# 31.net
KiCad netlist of a schematic drawn in Altium Designer
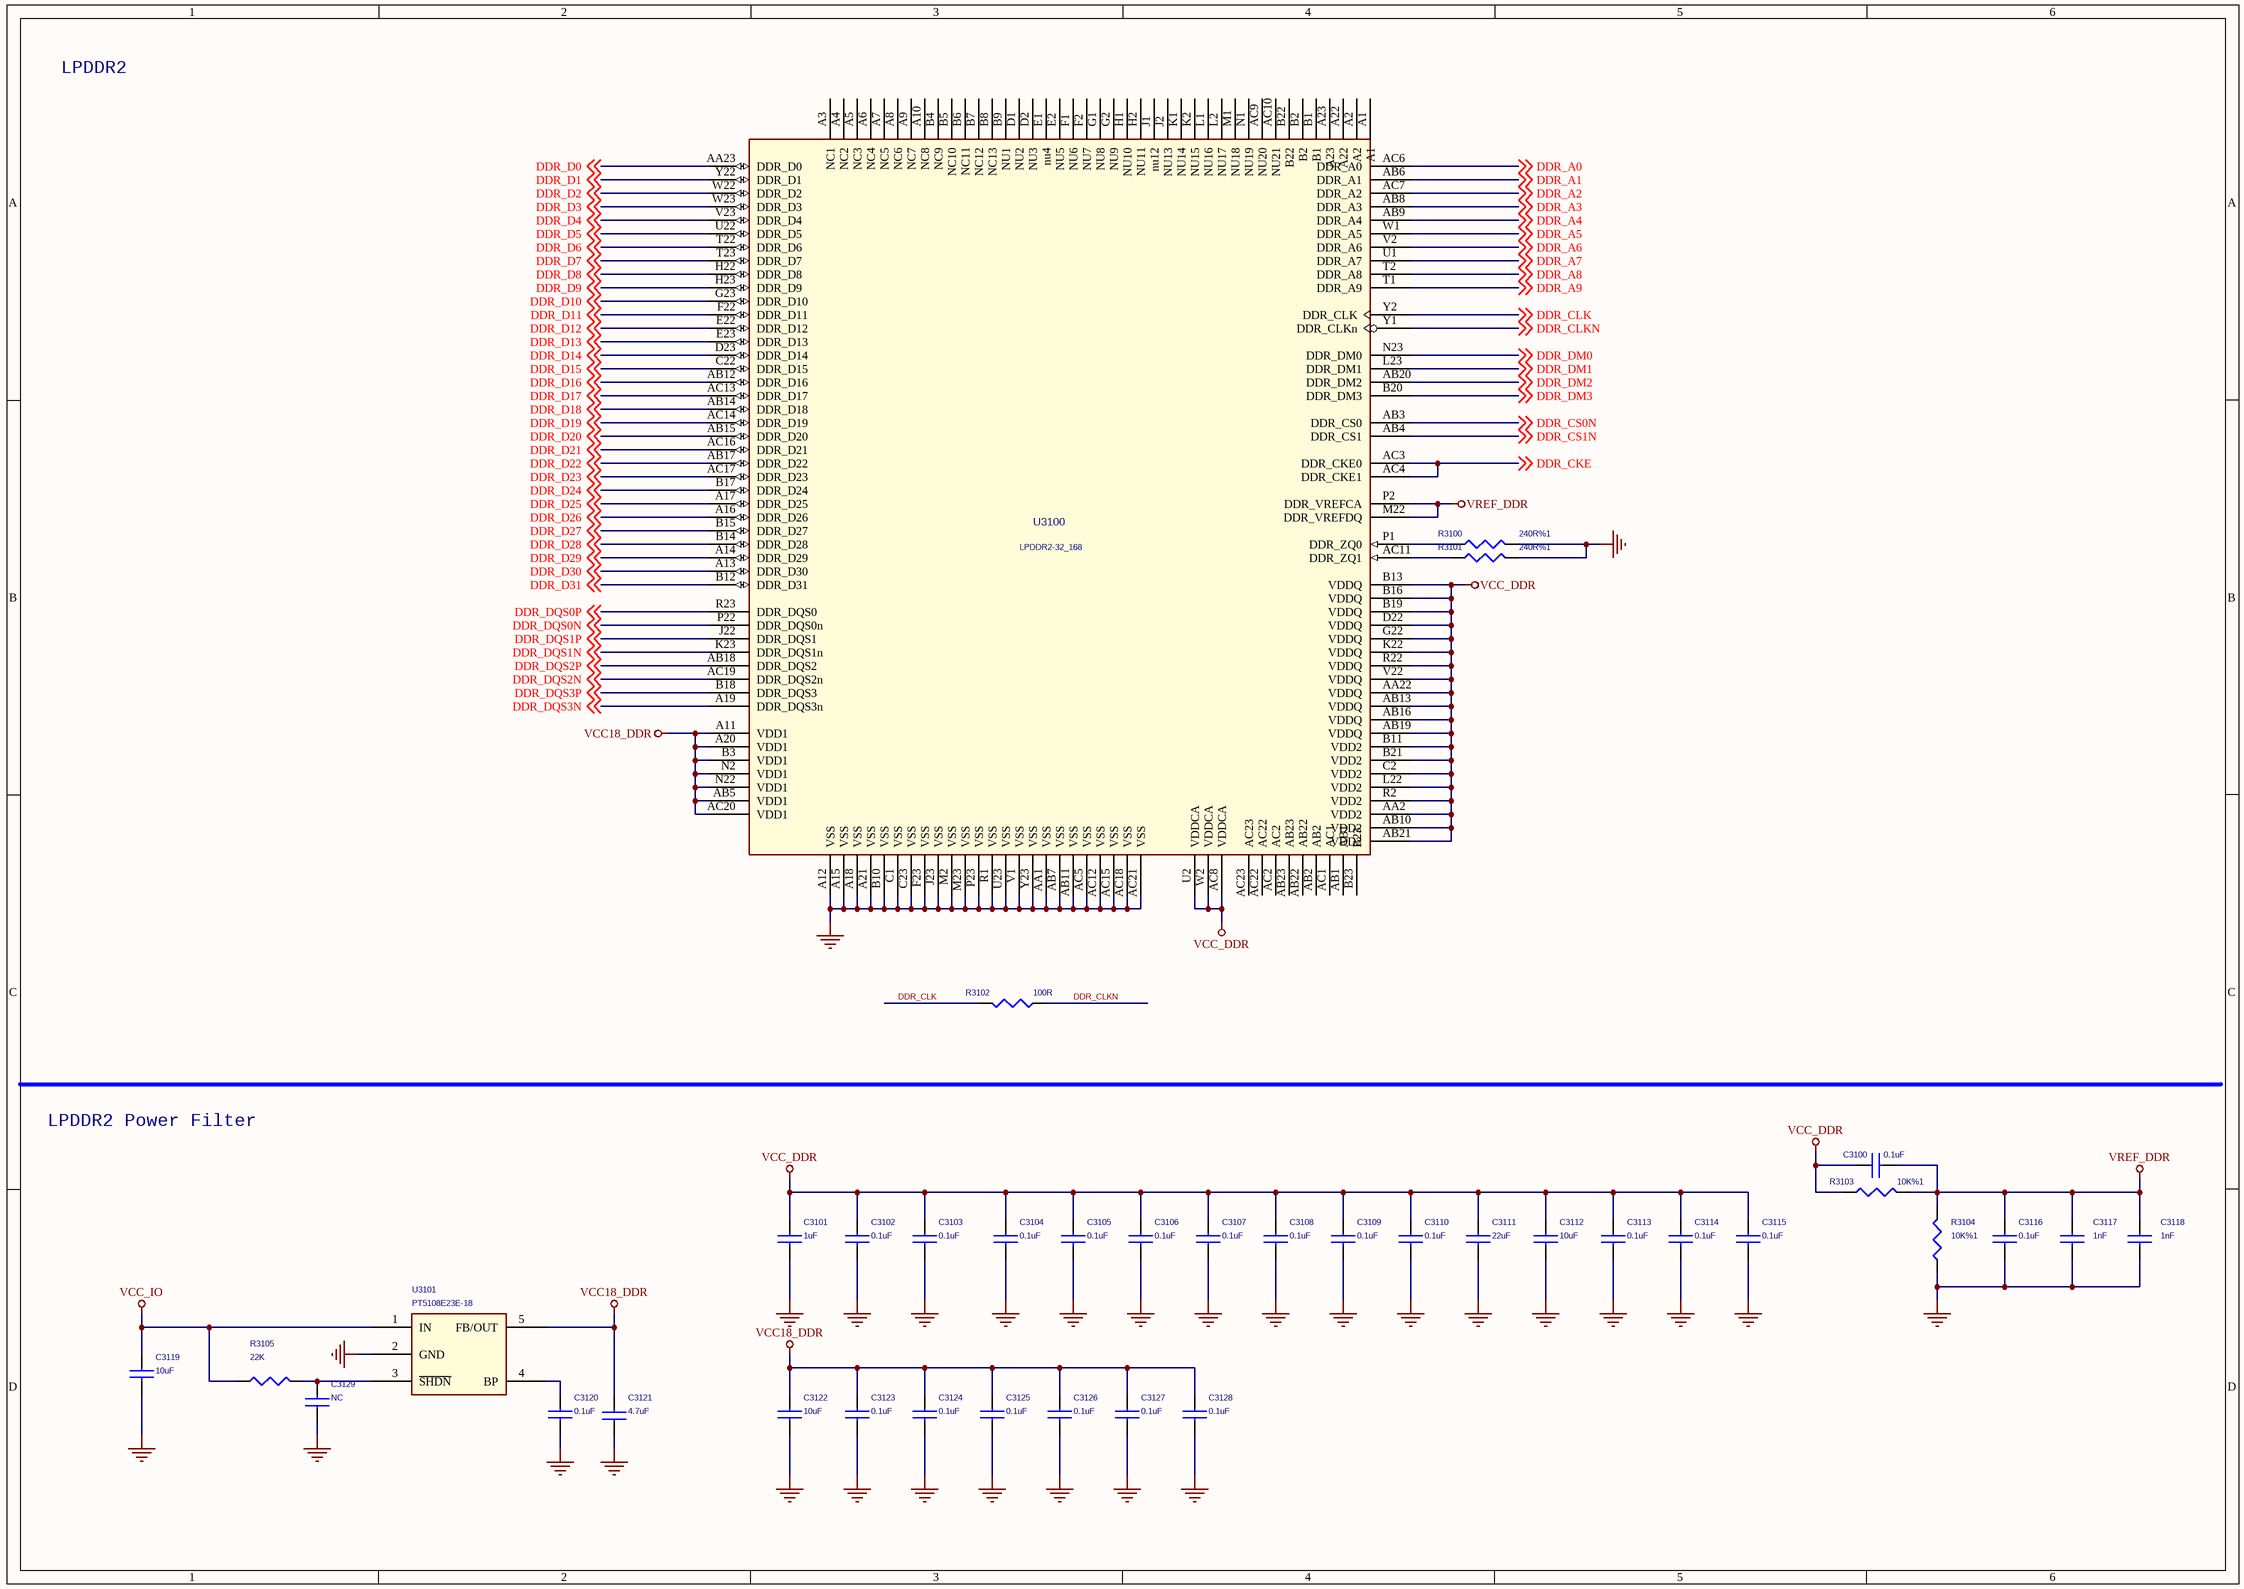
[diagram p0: 31.SchDoc]

(export (version "E")
  (design (tool "Eeschema 10.0.6"))
  (components
    (comp (ref "C3100") (value "0.1uF") (footprint "C0402") (libsource (lib "*") (part "CAP NP_0")))
    (comp (ref "C3101")
      (value "1uF")
      (footprint "C0402")
      (description "RoHS CHIP CAP 1uF +10/-10% X5R")
      (libsource (lib "*") (part "CAP NP"))
    )
    (comp (ref "C3102")
      (value "0.1uF")
      (footprint "C0402")
      (description "RoHS CHIP CAP 1uF +10/-10% X5R")
      (libsource (lib "*") (part "CAP NP"))
    )
    (comp (ref "C3103")
      (value "0.1uF")
      (footprint "C0402")
      (description "RoHS CHIP CAP 0.1uF +10/-10% X7R")
      (libsource (lib "*") (part "CAP NP"))
    )
    (comp (ref "C3104")
      (value "0.1uF")
      (footprint "C0402")
      (description "RoHS CHIP CAP 0.1uF +10/-10% X7R")
      (libsource (lib "*") (part "CAP NP"))
    )
    (comp (ref "C3105")
      (value "0.1uF")
      (footprint "C0402")
      (description "RoHS CHIP CAP 0.1uF +10/-10% X7R")
      (libsource (lib "*") (part "CAP NP"))
    )
    (comp (ref "C3106")
      (value "0.1uF")
      (footprint "C0402")
      (description "RoHS CHIP CAP 0.1uF +10/-10% X7R")
      (libsource (lib "*") (part "CAP NP"))
    )
    (comp (ref "C3107")
      (value "0.1uF")
      (footprint "C0402")
      (description "RoHS CHIP CAP 0.1uF +10/-10% X7R")
      (libsource (lib "*") (part "CAP NP"))
    )
    (comp (ref "C3108")
      (value "0.1uF")
      (footprint "C0402")
      (description "RoHS CHIP CAP 0.1uF +10/-10% X7R")
      (libsource (lib "*") (part "CAP NP"))
    )
    (comp (ref "C3109")
      (value "0.1uF")
      (footprint "C0402")
      (description "RoHS CHIP CAP 0.1uF +10/-10% X7R")
      (libsource (lib "*") (part "CAP NP"))
    )
    (comp (ref "C3110")
      (value "0.1uF")
      (footprint "C0402")
      (description "RoHS CHIP CAP 0.1uF +10/-10% X7R")
      (libsource (lib "*") (part "CAP NP"))
    )
    (comp (ref "C3111")
      (value "22uF")
      (footprint "C0402")
      (description "RoHS CHIP CAP 0.1uF +10/-10% X7R")
      (libsource (lib "*") (part "CAP NP"))
    )
    (comp (ref "C3112")
      (value "10uF")
      (footprint "C0402")
      (description "RoHS CHIP CAP 0.1uF +10/-10% X7R")
      (libsource (lib "*") (part "CAP NP"))
    )
    (comp (ref "C3113")
      (value "0.1uF")
      (footprint "C0402")
      (description "RoHS CHIP CAP 0.1uF +10/-10% X7R")
      (libsource (lib "*") (part "CAP NP"))
    )
    (comp (ref "C3114")
      (value "0.1uF")
      (footprint "C0402")
      (description "RoHS CHIP CAP 0.1uF +10/-10% X7R")
      (libsource (lib "*") (part "CAP NP"))
    )
    (comp (ref "C3115")
      (value "0.1uF")
      (footprint "C0402")
      (description "RoHS CHIP CAP 0.1uF +10/-10% X7R")
      (libsource (lib "*") (part "CAP NP"))
    )
    (comp (ref "C3116") (value "0.1uF") (footprint "C0402") (libsource (lib "*") (part "CAP NP_0")))
    (comp (ref "C3117") (value "1nF") (footprint "C0402") (libsource (lib "*") (part "CAP NP_0")))
    (comp (ref "C3118") (value "1nF") (footprint "C0402") (libsource (lib "*") (part "CAP NP_0")))
    (comp (ref "C3119")
      (value "10uF")
      (footprint "C0402")
      (description "CAP,MLCC,22uF,+/-10%,X5R,6.3V,SMD1206")
      (libsource (lib "*") (part "CAP NP"))
    )
    (comp (ref "C3120")
      (value "0.1uF")
      (footprint "C0402")
      (description "CAP,MLCC,100nF,+/-10%,X7R,6.3V,SMD0402")
      (libsource (lib "*") (part "CAP NP"))
    )
    (comp (ref "C3121")
      (value "4.7uF")
      (footprint "C0402")
      (description "CAP,MLCC,10uF,+/-10%,X5R,6.3V,SMD0805")
      (libsource (lib "*") (part "CAP NP"))
    )
    (comp (ref "C3122")
      (value "10uF")
      (footprint "C0402")
      (description "RoHS CHIP CAP 1uF +10/-10% X5R")
      (libsource (lib "*") (part "CAP NP"))
    )
    (comp (ref "C3123")
      (value "0.1uF")
      (footprint "C0402")
      (description "RoHS CHIP CAP 0.1uF +10/-10% X7R")
      (libsource (lib "*") (part "CAP NP"))
    )
    (comp (ref "C3124")
      (value "0.1uF")
      (footprint "C0402")
      (description "RoHS CHIP CAP 0.1uF +10/-10% X7R")
      (libsource (lib "*") (part "CAP NP"))
    )
    (comp (ref "C3125")
      (value "0.1uF")
      (footprint "C0402")
      (description "RoHS CHIP CAP 0.1uF +10/-10% X7R")
      (libsource (lib "*") (part "CAP NP"))
    )
    (comp (ref "C3126")
      (value "0.1uF")
      (footprint "C0402")
      (description "RoHS CHIP CAP 0.1uF +10/-10% X7R")
      (libsource (lib "*") (part "CAP NP"))
    )
    (comp (ref "C3127")
      (value "0.1uF")
      (footprint "C0402")
      (description "RoHS CHIP CAP 0.1uF +10/-10% X7R")
      (libsource (lib "*") (part "CAP NP"))
    )
    (comp (ref "C3128")
      (value "0.1uF")
      (footprint "C0402")
      (description "RoHS CHIP CAP 0.1uF +10/-10% X7R")
      (libsource (lib "*") (part "CAP NP"))
    )
    (comp (ref "C3129") (value "NC") (footprint "C0402") (libsource (lib "*") (part "CAP NP")))
    (comp (ref "R3100")
      (value "240R%1")
      (footprint "R0402")
      (description "贴片电阻")
      (libsource (lib "*") (part "RESISTOR_0"))
    )
    (comp (ref "R3101")
      (value "240R%1")
      (footprint "R0402")
      (description "贴片电阻")
      (libsource (lib "*") (part "RESISTOR_0"))
    )
    (comp (ref "R3102")
      (value "100R")
      (footprint "R0402")
      (description "NC/ROHS CHIP RES 100R 1/16W 5%")
      (libsource (lib "*") (part "RESISTOR"))
    )
    (comp (ref "R3103")
      (value "10K%1")
      (footprint "R0402")
      (description "贴片电阻")
      (libsource (lib "*") (part "RESISTOR_0"))
    )
    (comp (ref "R3104")
      (value "10K%1")
      (footprint "R0402")
      (description "贴片电阻")
      (libsource (lib "*") (part "RESISTOR_0"))
    )
    (comp (ref "R3105") (value "22K") (footprint "R0402") (libsource (lib "*") (part "RES 1B")))
    (comp (ref "U3100")
      (value "LPDDR2-32_168")
      (footprint "BGA134")
      (libsource (lib "*") (part "LPDDR2-32_2"))
    )
    (comp (ref "U3101")
      (value "PT5108E23E-18")
      (footprint "SOT25")
      (description "LDO,PT5108E23E-18,VINmax=5.5V,Vout=1.8V,+/-2%,500mA,SOT-23-5")
      (libsource (lib "*") (part "DS8008_4"))
    )
  )
  (nets
    (net (code "1") (name "DDR_A0") (class "Default")
      (node (ref "U3100") (pin "AC6") (pinfunction "DDR_A0_AC6") (pintype "passive"))
    )
    (net (code "2") (name "DDR_A1") (class "Default")
      (node (ref "U3100") (pin "AB6") (pinfunction "DDR_A1_AB6") (pintype "passive"))
    )
    (net (code "3") (name "DDR_A2") (class "Default")
      (node (ref "U3100") (pin "AC7") (pinfunction "DDR_A2_AC7") (pintype "passive"))
    )
    (net (code "4") (name "DDR_A3") (class "Default")
      (node (ref "U3100") (pin "AB8") (pinfunction "DDR_A3_AB8") (pintype "passive"))
    )
    (net (code "5") (name "DDR_A4") (class "Default")
      (node (ref "U3100") (pin "AB9") (pinfunction "DDR_A4_AB9") (pintype "passive"))
    )
    (net (code "6") (name "DDR_A5") (class "Default")
      (node (ref "U3100") (pin "W1") (pinfunction "DDR_A5_W1") (pintype "passive"))
    )
    (net (code "7") (name "DDR_A6") (class "Default")
      (node (ref "U3100") (pin "V2") (pinfunction "DDR_A6_V2") (pintype "passive"))
    )
    (net (code "8") (name "DDR_A7") (class "Default")
      (node (ref "U3100") (pin "U1") (pinfunction "DDR_A7_U1") (pintype "passive"))
    )
    (net (code "9") (name "DDR_A8") (class "Default")
      (node (ref "U3100") (pin "T2") (pinfunction "DDR_A8_T2") (pintype "passive"))
    )
    (net (code "10") (name "DDR_A9") (class "Default")
      (node (ref "U3100") (pin "T1") (pinfunction "DDR_A9_T1") (pintype "passive"))
    )
    (net (code "11") (name "DDR_CKE") (class "Default")
      (node (ref "U3100") (pin "AC3") (pinfunction "DDR_CKE0_AC3") (pintype "passive"))
      (node (ref "U3100") (pin "AC4") (pinfunction "DDR_CKE1_AC4") (pintype "passive"))
    )
    (net (code "12") (name "DDR_CLK") (class "Default")
      (node (ref "R3102") (pin "2") (pinfunction "2_2") (pintype "passive"))
      (node (ref "U3100") (pin "Y2") (pinfunction "DDR_CLK_Y2") (pintype "passive"))
    )
    (net (code "13") (name "DDR_CLKN") (class "Default")
      (node (ref "R3102") (pin "1") (pinfunction "1_1") (pintype "passive"))
      (node (ref "U3100") (pin "Y1") (pinfunction "DDR_CLKn_Y1") (pintype "passive"))
    )
    (net (code "14") (name "DDR_CS0N") (class "Default")
      (node (ref "U3100") (pin "AB3") (pinfunction "DDR_CS0_AB3") (pintype "passive"))
    )
    (net (code "15") (name "DDR_CS1N") (class "Default")
      (node (ref "U3100") (pin "AB4") (pinfunction "DDR_CS1_AB4") (pintype "passive"))
    )
    (net (code "16") (name "DDR_D0") (class "Default")
      (node (ref "U3100") (pin "AA23") (pinfunction "DDR_D0_AA23") (pintype "bidirectional"))
    )
    (net (code "17") (name "DDR_D1") (class "Default")
      (node (ref "U3100") (pin "Y22") (pinfunction "DDR_D1_Y22") (pintype "bidirectional"))
    )
    (net (code "18") (name "DDR_D2") (class "Default")
      (node (ref "U3100") (pin "W22") (pinfunction "DDR_D2_W22") (pintype "bidirectional"))
    )
    (net (code "19") (name "DDR_D3") (class "Default")
      (node (ref "U3100") (pin "W23") (pinfunction "DDR_D3_W23") (pintype "bidirectional"))
    )
    (net (code "20") (name "DDR_D4") (class "Default")
      (node (ref "U3100") (pin "V23") (pinfunction "DDR_D4_V23") (pintype "bidirectional"))
    )
    (net (code "21") (name "DDR_D5") (class "Default")
      (node (ref "U3100") (pin "U22") (pinfunction "DDR_D5_U22") (pintype "bidirectional"))
    )
    (net (code "22") (name "DDR_D6") (class "Default")
      (node (ref "U3100") (pin "T22") (pinfunction "DDR_D6_T22") (pintype "bidirectional"))
    )
    (net (code "23") (name "DDR_D7") (class "Default")
      (node (ref "U3100") (pin "T23") (pinfunction "DDR_D7_T23") (pintype "bidirectional"))
    )
    (net (code "24") (name "DDR_D8") (class "Default")
      (node (ref "U3100") (pin "H22") (pinfunction "DDR_D8_H22") (pintype "bidirectional"))
    )
    (net (code "25") (name "DDR_D9") (class "Default")
      (node (ref "U3100") (pin "H23") (pinfunction "DDR_D9_H23") (pintype "bidirectional"))
    )
    (net (code "26") (name "DDR_D10") (class "Default")
      (node (ref "U3100") (pin "G23") (pinfunction "DDR_D10_G23") (pintype "bidirectional"))
    )
    (net (code "27") (name "DDR_D11") (class "Default")
      (node (ref "U3100") (pin "F22") (pinfunction "DDR_D11_F22") (pintype "bidirectional"))
    )
    (net (code "28") (name "DDR_D12") (class "Default")
      (node (ref "U3100") (pin "E22") (pinfunction "DDR_D12_E22") (pintype "bidirectional"))
    )
    (net (code "29") (name "DDR_D13") (class "Default")
      (node (ref "U3100") (pin "E23") (pinfunction "DDR_D13_E23") (pintype "bidirectional"))
    )
    (net (code "30") (name "DDR_D14") (class "Default")
      (node (ref "U3100") (pin "D23") (pinfunction "DDR_D14_D23") (pintype "bidirectional"))
    )
    (net (code "31") (name "DDR_D15") (class "Default")
      (node (ref "U3100") (pin "C22") (pinfunction "DDR_D15_C22") (pintype "bidirectional"))
    )
    (net (code "32") (name "DDR_D16") (class "Default")
      (node (ref "U3100") (pin "AB12") (pinfunction "DDR_D16_AB12") (pintype "bidirectional"))
    )
    (net (code "33") (name "DDR_D17") (class "Default")
      (node (ref "U3100") (pin "AC13") (pinfunction "DDR_D17_AC13") (pintype "bidirectional"))
    )
    (net (code "34") (name "DDR_D18") (class "Default")
      (node (ref "U3100") (pin "AB14") (pinfunction "DDR_D18_AB14") (pintype "bidirectional"))
    )
    (net (code "35") (name "DDR_D19") (class "Default")
      (node (ref "U3100") (pin "AC14") (pinfunction "DDR_D19_AC14") (pintype "bidirectional"))
    )
    (net (code "36") (name "DDR_D20") (class "Default")
      (node (ref "U3100") (pin "AB15") (pinfunction "DDR_D20_AB15") (pintype "bidirectional"))
    )
    (net (code "37") (name "DDR_D21") (class "Default")
      (node (ref "U3100") (pin "AC16") (pinfunction "DDR_D21_AC16") (pintype "bidirectional"))
    )
    (net (code "38") (name "DDR_D22") (class "Default")
      (node (ref "U3100") (pin "AB17") (pinfunction "DDR_D22_AB17") (pintype "bidirectional"))
    )
    (net (code "39") (name "DDR_D23") (class "Default")
      (node (ref "U3100") (pin "AC17") (pinfunction "DDR_D23_AC17") (pintype "bidirectional"))
    )
    (net (code "40") (name "DDR_D24") (class "Default")
      (node (ref "U3100") (pin "B17") (pinfunction "DDR_D24_B17") (pintype "bidirectional"))
    )
    (net (code "41") (name "DDR_D25") (class "Default")
      (node (ref "U3100") (pin "A17") (pinfunction "DDR_D25_A17") (pintype "bidirectional"))
    )
    (net (code "42") (name "DDR_D26") (class "Default")
      (node (ref "U3100") (pin "A16") (pinfunction "DDR_D26_A16") (pintype "bidirectional"))
    )
    (net (code "43") (name "DDR_D27") (class "Default")
      (node (ref "U3100") (pin "B15") (pinfunction "DDR_D27_B15") (pintype "bidirectional"))
    )
    (net (code "44") (name "DDR_D28") (class "Default")
      (node (ref "U3100") (pin "B14") (pinfunction "DDR_D28_B14") (pintype "bidirectional"))
    )
    (net (code "45") (name "DDR_D29") (class "Default")
      (node (ref "U3100") (pin "A14") (pinfunction "DDR_D29_A14") (pintype "bidirectional"))
    )
    (net (code "46") (name "DDR_D30") (class "Default")
      (node (ref "U3100") (pin "A13") (pinfunction "DDR_D30_A13") (pintype "bidirectional"))
    )
    (net (code "47") (name "DDR_D31") (class "Default")
      (node (ref "U3100") (pin "B12") (pinfunction "DDR_D31_B12") (pintype "bidirectional"))
    )
    (net (code "48") (name "DDR_DM0") (class "Default")
      (node (ref "U3100") (pin "N23") (pinfunction "DDR_DM0_N23") (pintype "passive"))
    )
    (net (code "49") (name "DDR_DM1") (class "Default")
      (node (ref "U3100") (pin "L23") (pinfunction "DDR_DM1_L23") (pintype "passive"))
    )
    (net (code "50") (name "DDR_DM2") (class "Default")
      (node (ref "U3100") (pin "AB20") (pinfunction "DDR_DM2_AB20") (pintype "passive"))
    )
    (net (code "51") (name "DDR_DM3") (class "Default")
      (node (ref "U3100") (pin "B20") (pinfunction "DDR_DM3_B20") (pintype "passive"))
    )
    (net (code "52") (name "DDR_DQS0N") (class "Default")
      (node (ref "U3100") (pin "P22") (pinfunction "DDR_DQS0n_P22") (pintype "passive"))
    )
    (net (code "53") (name "DDR_DQS0P") (class "Default")
      (node (ref "U3100") (pin "R23") (pinfunction "DDR_DQS0_R23") (pintype "passive"))
    )
    (net (code "54") (name "DDR_DQS1N") (class "Default")
      (node (ref "U3100") (pin "K23") (pinfunction "DDR_DQS1n_K23") (pintype "passive"))
    )
    (net (code "55") (name "DDR_DQS1P") (class "Default")
      (node (ref "U3100") (pin "J22") (pinfunction "DDR_DQS1_J22") (pintype "passive"))
    )
    (net (code "56") (name "DDR_DQS2N") (class "Default")
      (node (ref "U3100") (pin "AC19") (pinfunction "DDR_DQS2n_AC19") (pintype "passive"))
    )
    (net (code "57") (name "DDR_DQS2P") (class "Default")
      (node (ref "U3100") (pin "AB18") (pinfunction "DDR_DQS2_AB18") (pintype "passive"))
    )
    (net (code "58") (name "DDR_DQS3N") (class "Default")
      (node (ref "U3100") (pin "A19") (pinfunction "DDR_DQS3n_A19") (pintype "passive"))
    )
    (net (code "59") (name "DDR_DQS3P") (class "Default")
      (node (ref "U3100") (pin "B18") (pinfunction "DDR_DQS3_B18") (pintype "passive"))
    )
    (net (code "60") (name "GND") (class "Default")
      (node (ref "C3101") (pin "2") (pinfunction "2_2") (pintype "passive"))
      (node (ref "C3102") (pin "2") (pinfunction "2_2") (pintype "passive"))
      (node (ref "C3103") (pin "2") (pinfunction "2_2") (pintype "passive"))
      (node (ref "C3104") (pin "2") (pinfunction "2_2") (pintype "passive"))
      (node (ref "C3105") (pin "2") (pinfunction "2_2") (pintype "passive"))
      (node (ref "C3106") (pin "2") (pinfunction "2_2") (pintype "passive"))
      (node (ref "C3107") (pin "2") (pinfunction "2_2") (pintype "passive"))
      (node (ref "C3108") (pin "2") (pinfunction "2_2") (pintype "passive"))
      (node (ref "C3109") (pin "2") (pinfunction "2_2") (pintype "passive"))
      (node (ref "C3110") (pin "2") (pinfunction "2_2") (pintype "passive"))
      (node (ref "C3111") (pin "2") (pinfunction "2_2") (pintype "passive"))
      (node (ref "C3112") (pin "2") (pinfunction "2_2") (pintype "passive"))
      (node (ref "C3113") (pin "2") (pinfunction "2_2") (pintype "passive"))
      (node (ref "C3114") (pin "2") (pinfunction "2_2") (pintype "passive"))
      (node (ref "C3115") (pin "2") (pinfunction "2_2") (pintype "passive"))
      (node (ref "C3116") (pin "2") (pinfunction "2_2") (pintype "passive"))
      (node (ref "C3117") (pin "2") (pinfunction "2_2") (pintype "passive"))
      (node (ref "C3118") (pin "2") (pinfunction "2_2") (pintype "passive"))
      (node (ref "C3119") (pin "2") (pinfunction "2_2") (pintype "passive"))
      (node (ref "C3120") (pin "2") (pinfunction "2_2") (pintype "passive"))
      (node (ref "C3121") (pin "1") (pinfunction "1_1") (pintype "passive"))
      (node (ref "C3122") (pin "2") (pinfunction "2_2") (pintype "passive"))
      (node (ref "C3123") (pin "2") (pinfunction "2_2") (pintype "passive"))
      (node (ref "C3124") (pin "2") (pinfunction "2_2") (pintype "passive"))
      (node (ref "C3125") (pin "2") (pinfunction "2_2") (pintype "passive"))
      (node (ref "C3126") (pin "2") (pinfunction "2_2") (pintype "passive"))
      (node (ref "C3127") (pin "2") (pinfunction "2_2") (pintype "passive"))
      (node (ref "C3128") (pin "2") (pinfunction "2_2") (pintype "passive"))
      (node (ref "C3129") (pin "1") (pinfunction "1_1") (pintype "passive"))
      (node (ref "R3100") (pin "2") (pinfunction "2_2") (pintype "passive"))
      (node (ref "R3101") (pin "2") (pinfunction "2_2") (pintype "passive"))
      (node (ref "R3104") (pin "1") (pinfunction "1_1") (pintype "passive"))
      (node (ref "U3100") (pin "A12") (pinfunction "VSS_A12") (pintype "power_in"))
      (node (ref "U3100") (pin "A15") (pinfunction "VSS_A15") (pintype "power_in"))
      (node (ref "U3100") (pin "A18") (pinfunction "VSS_A18") (pintype "power_in"))
      (node (ref "U3100") (pin "A21") (pinfunction "VSS_A21") (pintype "power_in"))
      (node (ref "U3100") (pin "AA1") (pinfunction "VSS_AA1") (pintype "power_in"))
      (node (ref "U3100") (pin "AB11") (pinfunction "VSS_AB11") (pintype "power_in"))
      (node (ref "U3100") (pin "AB7") (pinfunction "VSS_AB7") (pintype "power_in"))
      (node (ref "U3100") (pin "AC12") (pinfunction "VSS_AC12") (pintype "power_in"))
      (node (ref "U3100") (pin "AC15") (pinfunction "VSS_AC15") (pintype "power_in"))
      (node (ref "U3100") (pin "AC18") (pinfunction "VSS_AC18") (pintype "power_in"))
      (node (ref "U3100") (pin "AC21") (pinfunction "VSS_AC21") (pintype "power_in"))
      (node (ref "U3100") (pin "AC5") (pinfunction "VSS_AC5") (pintype "power_in"))
      (node (ref "U3100") (pin "B10") (pinfunction "VSS_B10") (pintype "power_in"))
      (node (ref "U3100") (pin "C1") (pinfunction "VSS_C1") (pintype "power_in"))
      (node (ref "U3100") (pin "C23") (pinfunction "VSS_C23") (pintype "power_in"))
      (node (ref "U3100") (pin "F23") (pinfunction "VSS_F23") (pintype "power_in"))
      (node (ref "U3100") (pin "J23") (pinfunction "VSS_J23") (pintype "power_in"))
      (node (ref "U3100") (pin "M2") (pinfunction "VSS_M2") (pintype "power_in"))
      (node (ref "U3100") (pin "M23") (pinfunction "VSS_M23") (pintype "power_in"))
      (node (ref "U3100") (pin "P23") (pinfunction "VSS_P23") (pintype "power_in"))
      (node (ref "U3100") (pin "R1") (pinfunction "VSS_R1") (pintype "power_in"))
      (node (ref "U3100") (pin "U23") (pinfunction "VSS_U23") (pintype "power_in"))
      (node (ref "U3100") (pin "V1") (pinfunction "VSS_V1") (pintype "power_in"))
      (node (ref "U3100") (pin "Y23") (pinfunction "VSS_Y23") (pintype "power_in"))
      (node (ref "U3101") (pin "2") (pinfunction "GND_2") (pintype "passive"))
    )
    (net (code "61") (name "Net-(U3100-DDR_ZQ0)") (class "Default")
      (node (ref "R3100") (pin "1") (pinfunction "1_1") (pintype "passive"))
      (node (ref "U3100") (pin "P1") (pinfunction "DDR_ZQ0_P1") (pintype "input"))
    )
    (net (code "62") (name "Net-(U3100-DDR_ZQ1)") (class "Default")
      (node (ref "R3101") (pin "1") (pinfunction "1_1") (pintype "passive"))
      (node (ref "U3100") (pin "AC11") (pinfunction "DDR_ZQ1_AC11") (pintype "input"))
    )
    (net (code "63") (name "Net-(U3101-BP)") (class "Default")
      (node (ref "C3120") (pin "1") (pinfunction "1_1") (pintype "passive"))
      (node (ref "U3101") (pin "4") (pinfunction "BP_4") (pintype "passive"))
    )
    (net (code "64") (name "Net-(U3101-~{SHDN})") (class "Default")
      (node (ref "C3129") (pin "2") (pinfunction "2_2") (pintype "passive"))
      (node (ref "R3105") (pin "2") (pinfunction "2_2") (pintype "passive"))
      (node (ref "U3101") (pin "3") (pinfunction "~{SHDN}_3") (pintype "passive"))
    )
    (net (code "65") (name "VCC18_DDR") (class "Default")
      (node (ref "C3121") (pin "2") (pinfunction "2_2") (pintype "passive"))
      (node (ref "C3122") (pin "1") (pinfunction "1_1") (pintype "passive"))
      (node (ref "C3123") (pin "1") (pinfunction "1_1") (pintype "passive"))
      (node (ref "C3124") (pin "1") (pinfunction "1_1") (pintype "passive"))
      (node (ref "C3125") (pin "1") (pinfunction "1_1") (pintype "passive"))
      (node (ref "C3126") (pin "1") (pinfunction "1_1") (pintype "passive"))
      (node (ref "C3127") (pin "1") (pinfunction "1_1") (pintype "passive"))
      (node (ref "C3128") (pin "1") (pinfunction "1_1") (pintype "passive"))
      (node (ref "U3100") (pin "A11") (pinfunction "VDD1_A11") (pintype "power_in"))
      (node (ref "U3100") (pin "A20") (pinfunction "VDD1_A20") (pintype "power_in"))
      (node (ref "U3100") (pin "AB5") (pinfunction "VDD1_AB5") (pintype "power_in"))
      (node (ref "U3100") (pin "AC20") (pinfunction "VDD1_AC20") (pintype "power_in"))
      (node (ref "U3100") (pin "B3") (pinfunction "VDD1_B3") (pintype "power_in"))
      (node (ref "U3100") (pin "N2") (pinfunction "VDD1_N2") (pintype "power_in"))
      (node (ref "U3100") (pin "N22") (pinfunction "VDD1_N22") (pintype "power_in"))
      (node (ref "U3101") (pin "5") (pinfunction "FB/OUT_5") (pintype "passive"))
    )
    (net (code "66") (name "VCC_DDR") (class "Default")
      (node (ref "C3100") (pin "1") (pinfunction "1_1") (pintype "passive"))
      (node (ref "C3101") (pin "1") (pinfunction "1_1") (pintype "passive"))
      (node (ref "C3102") (pin "1") (pinfunction "1_1") (pintype "passive"))
      (node (ref "C3103") (pin "1") (pinfunction "1_1") (pintype "passive"))
      (node (ref "C3104") (pin "1") (pinfunction "1_1") (pintype "passive"))
      (node (ref "C3105") (pin "1") (pinfunction "1_1") (pintype "passive"))
      (node (ref "C3106") (pin "1") (pinfunction "1_1") (pintype "passive"))
      (node (ref "C3107") (pin "1") (pinfunction "1_1") (pintype "passive"))
      (node (ref "C3108") (pin "1") (pinfunction "1_1") (pintype "passive"))
      (node (ref "C3109") (pin "1") (pinfunction "1_1") (pintype "passive"))
      (node (ref "C3110") (pin "1") (pinfunction "1_1") (pintype "passive"))
      (node (ref "C3111") (pin "1") (pinfunction "1_1") (pintype "passive"))
      (node (ref "C3112") (pin "1") (pinfunction "1_1") (pintype "passive"))
      (node (ref "C3113") (pin "1") (pinfunction "1_1") (pintype "passive"))
      (node (ref "C3114") (pin "1") (pinfunction "1_1") (pintype "passive"))
      (node (ref "C3115") (pin "1") (pinfunction "1_1") (pintype "passive"))
      (node (ref "R3103") (pin "1") (pinfunction "1_1") (pintype "passive"))
      (node (ref "U3100") (pin "AA2") (pinfunction "VDD2_AA2") (pintype "power_in"))
      (node (ref "U3100") (pin "AA22") (pinfunction "VDDQ_AA22") (pintype "power_in"))
      (node (ref "U3100") (pin "AB10") (pinfunction "VDD2_AB10") (pintype "power_in"))
      (node (ref "U3100") (pin "AB13") (pinfunction "VDDQ_AB13") (pintype "power_in"))
      (node (ref "U3100") (pin "AB16") (pinfunction "VDDQ_AB16") (pintype "power_in"))
      (node (ref "U3100") (pin "AB19") (pinfunction "VDDQ_AB19") (pintype "power_in"))
      (node (ref "U3100") (pin "AB21") (pinfunction "VDD2_AB21") (pintype "power_in"))
      (node (ref "U3100") (pin "AC8") (pinfunction "VDDCA_AC8") (pintype "power_in"))
      (node (ref "U3100") (pin "B11") (pinfunction "VDD2_B11") (pintype "power_in"))
      (node (ref "U3100") (pin "B13") (pinfunction "VDDQ_B13") (pintype "power_in"))
      (node (ref "U3100") (pin "B16") (pinfunction "VDDQ_B16") (pintype "power_in"))
      (node (ref "U3100") (pin "B19") (pinfunction "VDDQ_B19") (pintype "power_in"))
      (node (ref "U3100") (pin "B21") (pinfunction "VDD2_B21") (pintype "power_in"))
      (node (ref "U3100") (pin "C2") (pinfunction "VDD2_C2") (pintype "power_in"))
      (node (ref "U3100") (pin "D22") (pinfunction "VDDQ_D22") (pintype "power_in"))
      (node (ref "U3100") (pin "G22") (pinfunction "VDDQ_G22") (pintype "power_in"))
      (node (ref "U3100") (pin "K22") (pinfunction "VDDQ_K22") (pintype "power_in"))
      (node (ref "U3100") (pin "L22") (pinfunction "VDD2_L22") (pintype "power_in"))
      (node (ref "U3100") (pin "R2") (pinfunction "VDD2_R2") (pintype "power_in"))
      (node (ref "U3100") (pin "R22") (pinfunction "VDDQ_R22") (pintype "power_in"))
      (node (ref "U3100") (pin "U2") (pinfunction "VDDCA_U2") (pintype "power_in"))
      (node (ref "U3100") (pin "V22") (pinfunction "VDDQ_V22") (pintype "power_in"))
      (node (ref "U3100") (pin "W2") (pinfunction "VDDCA_W2") (pintype "power_in"))
    )
    (net (code "67") (name "VCC_IO") (class "Default")
      (node (ref "C3119") (pin "1") (pinfunction "1_1") (pintype "passive"))
      (node (ref "R3105") (pin "1") (pinfunction "1_1") (pintype "passive"))
      (node (ref "U3101") (pin "1") (pinfunction "IN_1") (pintype "passive"))
    )
    (net (code "68") (name "VREF_DDR") (class "Default")
      (node (ref "C3100") (pin "2") (pinfunction "2_2") (pintype "passive"))
      (node (ref "C3116") (pin "1") (pinfunction "1_1") (pintype "passive"))
      (node (ref "C3117") (pin "1") (pinfunction "1_1") (pintype "passive"))
      (node (ref "C3118") (pin "1") (pinfunction "1_1") (pintype "passive"))
      (node (ref "R3103") (pin "2") (pinfunction "2_2") (pintype "passive"))
      (node (ref "R3104") (pin "2") (pinfunction "2_2") (pintype "passive"))
      (node (ref "U3100") (pin "M22") (pinfunction "DDR_VREFDQ_M22") (pintype "power_in"))
      (node (ref "U3100") (pin "P2") (pinfunction "DDR_VREFCA_P2") (pintype "passive"))
    )
    (net (code "69") (name "unconnected-(U3100-NC1-PadA3)") (class "Default")
      (node (ref "U3100") (pin "A3") (pinfunction "NC1_A3") (pintype "passive"))
    )
    (net (code "70") (name "unconnected-(U3100-NC2-PadA4)") (class "Default")
      (node (ref "U3100") (pin "A4") (pinfunction "NC2_A4") (pintype "passive"))
    )
    (net (code "71") (name "unconnected-(U3100-NC3-PadA5)") (class "Default")
      (node (ref "U3100") (pin "A5") (pinfunction "NC3_A5") (pintype "passive"))
    )
    (net (code "72") (name "unconnected-(U3100-NC4-PadA6)") (class "Default")
      (node (ref "U3100") (pin "A6") (pinfunction "NC4_A6") (pintype "passive"))
    )
    (net (code "73") (name "unconnected-(U3100-NC5-PadA7)") (class "Default")
      (node (ref "U3100") (pin "A7") (pinfunction "NC5_A7") (pintype "passive"))
    )
    (net (code "74") (name "unconnected-(U3100-NC6-PadA8)") (class "Default")
      (node (ref "U3100") (pin "A8") (pinfunction "NC6_A8") (pintype "passive"))
    )
    (net (code "75") (name "unconnected-(U3100-NC7-PadA9)") (class "Default")
      (node (ref "U3100") (pin "A9") (pinfunction "NC7_A9") (pintype "passive"))
    )
    (net (code "76") (name "unconnected-(U3100-NC8-PadA10)") (class "Default")
      (node (ref "U3100") (pin "A10") (pinfunction "NC8_A10") (pintype "passive"))
    )
    (net (code "77") (name "unconnected-(U3100-NC9-PadB4)") (class "Default")
      (node (ref "U3100") (pin "B4") (pinfunction "NC9_B4") (pintype "passive"))
    )
    (net (code "78") (name "unconnected-(U3100-NC10-PadB5)") (class "Default")
      (node (ref "U3100") (pin "B5") (pinfunction "NC10_B5") (pintype "passive"))
    )
    (net (code "79") (name "unconnected-(U3100-NC11-PadB6)") (class "Default")
      (node (ref "U3100") (pin "B6") (pinfunction "NC11_B6") (pintype "passive"))
    )
    (net (code "80") (name "unconnected-(U3100-NC12-PadB7)") (class "Default")
      (node (ref "U3100") (pin "B7") (pinfunction "NC12_B7") (pintype "passive"))
    )
    (net (code "81") (name "unconnected-(U3100-NC13-PadB8)") (class "Default")
      (node (ref "U3100") (pin "B8") (pinfunction "NC13_B8") (pintype "passive"))
    )
    (net (code "82") (name "unconnected-(U3100-NU1-PadB9)") (class "Default")
      (node (ref "U3100") (pin "B9") (pinfunction "NU1_B9") (pintype "passive"))
    )
    (net (code "83") (name "unconnected-(U3100-NU2-PadD1)") (class "Default")
      (node (ref "U3100") (pin "D1") (pinfunction "NU2_D1") (pintype "passive"))
    )
    (net (code "84") (name "unconnected-(U3100-NU3-PadD2)") (class "Default")
      (node (ref "U3100") (pin "D2") (pinfunction "NU3_D2") (pintype "passive"))
    )
    (net (code "85") (name "unconnected-(U3100-NU5-PadE2)") (class "Default")
      (node (ref "U3100") (pin "E2") (pinfunction "NU5_E2") (pintype "passive"))
    )
    (net (code "86") (name "unconnected-(U3100-NU6-PadF1)") (class "Default")
      (node (ref "U3100") (pin "F1") (pinfunction "NU6_F1") (pintype "passive"))
    )
    (net (code "87") (name "unconnected-(U3100-NU7-PadF2)") (class "Default")
      (node (ref "U3100") (pin "F2") (pinfunction "NU7_F2") (pintype "passive"))
    )
    (net (code "88") (name "unconnected-(U3100-NU8-PadG1)") (class "Default")
      (node (ref "U3100") (pin "G1") (pinfunction "NU8_G1") (pintype "passive"))
    )
    (net (code "89") (name "unconnected-(U3100-NU9-PadG2)") (class "Default")
      (node (ref "U3100") (pin "G2") (pinfunction "NU9_G2") (pintype "passive"))
    )
    (net (code "90") (name "unconnected-(U3100-NU10-PadH1)") (class "Default")
      (node (ref "U3100") (pin "H1") (pinfunction "NU10_H1") (pintype "passive"))
    )
    (net (code "91") (name "unconnected-(U3100-NU11-PadH2)") (class "Default")
      (node (ref "U3100") (pin "H2") (pinfunction "NU11_H2") (pintype "passive"))
    )
    (net (code "92") (name "unconnected-(U3100-NU13-PadJ2)") (class "Default")
      (node (ref "U3100") (pin "J2") (pinfunction "NU13_J2") (pintype "passive"))
    )
    (net (code "93") (name "unconnected-(U3100-NU14-PadK1)") (class "Default")
      (node (ref "U3100") (pin "K1") (pinfunction "NU14_K1") (pintype "passive"))
    )
    (net (code "94") (name "unconnected-(U3100-NU15-PadK2)") (class "Default")
      (node (ref "U3100") (pin "K2") (pinfunction "NU15_K2") (pintype "passive"))
    )
    (net (code "95") (name "unconnected-(U3100-NU16-PadL1)") (class "Default")
      (node (ref "U3100") (pin "L1") (pinfunction "NU16_L1") (pintype "passive"))
    )
    (net (code "96") (name "unconnected-(U3100-NU17-PadL2)") (class "Default")
      (node (ref "U3100") (pin "L2") (pinfunction "NU17_L2") (pintype "passive"))
    )
    (net (code "97") (name "unconnected-(U3100-NU18-PadM1)") (class "Default")
      (node (ref "U3100") (pin "M1") (pinfunction "NU18_M1") (pintype "passive"))
    )
    (net (code "98") (name "unconnected-(U3100-NU19-PadN1)") (class "Default")
      (node (ref "U3100") (pin "N1") (pinfunction "NU19_N1") (pintype "passive"))
    )
    (net (code "99") (name "unconnected-(U3100-NU20-PadAC9)") (class "Default")
      (node (ref "U3100") (pin "AC9") (pinfunction "NU20_AC9") (pintype "passive"))
    )
    (net (code "100") (name "unconnected-(U3100-NU21-PadAC10)") (class "Default")
      (node (ref "U3100") (pin "AC10") (pinfunction "NU21_AC10") (pintype "passive"))
    )
    (net (code "101") (name "unconnected-(U3100-PadA1)") (class "Default")
      (node (ref "U3100") (pin "A1") (pinfunction "A1_A1") (pintype "passive"))
    )
    (net (code "102") (name "unconnected-(U3100-PadA2)") (class "Default")
      (node (ref "U3100") (pin "A2") (pinfunction "A2_A2") (pintype "passive"))
    )
    (net (code "103") (name "unconnected-(U3100-PadA22)") (class "Default")
      (node (ref "U3100") (pin "A22") (pinfunction "A22_A22") (pintype "passive"))
    )
    (net (code "104") (name "unconnected-(U3100-PadA23)") (class "Default")
      (node (ref "U3100") (pin "A23") (pinfunction "A23_A23") (pintype "passive"))
    )
    (net (code "105") (name "unconnected-(U3100-PadAB1)") (class "Default")
      (node (ref "U3100") (pin "AB1") (pinfunction "AB1_AB1") (pintype "power_in"))
    )
    (net (code "106") (name "unconnected-(U3100-PadAB2)") (class "Default")
      (node (ref "U3100") (pin "AB2") (pinfunction "AB2_AB2") (pintype "power_in"))
    )
    (net (code "107") (name "unconnected-(U3100-PadAB22)") (class "Default")
      (node (ref "U3100") (pin "AB22") (pinfunction "AB22_AB22") (pintype "power_in"))
    )
    (net (code "108") (name "unconnected-(U3100-PadAB23)") (class "Default")
      (node (ref "U3100") (pin "AB23") (pinfunction "AB23_AB23") (pintype "power_in"))
    )
    (net (code "109") (name "unconnected-(U3100-PadAC1)") (class "Default")
      (node (ref "U3100") (pin "AC1") (pinfunction "AC1_AC1") (pintype "power_in"))
    )
    (net (code "110") (name "unconnected-(U3100-PadAC2)") (class "Default")
      (node (ref "U3100") (pin "AC2") (pinfunction "AC2_AC2") (pintype "power_in"))
    )
    (net (code "111") (name "unconnected-(U3100-PadAC22)") (class "Default")
      (node (ref "U3100") (pin "AC22") (pinfunction "AC22_AC22") (pintype "power_in"))
    )
    (net (code "112") (name "unconnected-(U3100-PadAC23)") (class "Default")
      (node (ref "U3100") (pin "AC23") (pinfunction "AC23_AC23") (pintype "power_in"))
    )
    (net (code "113") (name "unconnected-(U3100-PadB1)") (class "Default")
      (node (ref "U3100") (pin "B1") (pinfunction "B1_B1") (pintype "passive"))
    )
    (net (code "114") (name "unconnected-(U3100-PadB2)") (class "Default")
      (node (ref "U3100") (pin "B2") (pinfunction "B2_B2") (pintype "passive"))
    )
    (net (code "115") (name "unconnected-(U3100-PadB22)") (class "Default")
      (node (ref "U3100") (pin "B22") (pinfunction "B22_B22") (pintype "passive"))
    )
    (net (code "116") (name "unconnected-(U3100-PadB23)") (class "Default")
      (node (ref "U3100") (pin "B23") (pinfunction "B23_B23") (pintype "power_in"))
    )
    (net (code "117") (name "unconnected-(U3100-nu4-PadE1)") (class "Default")
      (node (ref "U3100") (pin "E1") (pinfunction "nu4_E1") (pintype "passive"))
    )
    (net (code "118") (name "unconnected-(U3100-nu12-PadJ1)") (class "Default")
      (node (ref "U3100") (pin "J1") (pinfunction "nu12_J1") (pintype "passive"))
    )
  )
)
